# User_LEDs.net
KiCad netlist of a schematic drawn in Altium Designer
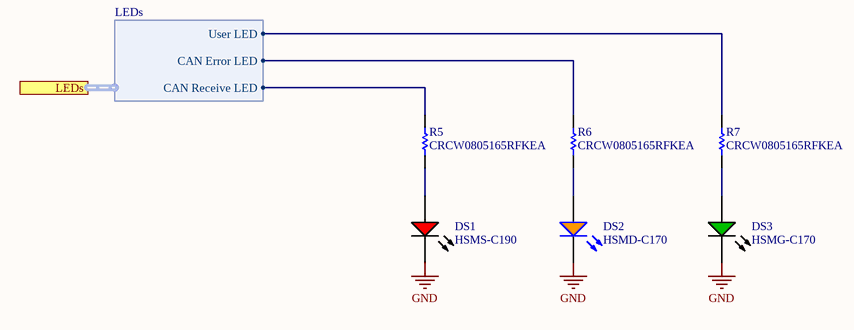
[diagram p0: User_LEDs.SchDoc]

(export (version "E")
  (design (tool "Eeschema 10.0.6"))
  (components
    (comp (ref "DS1")
      (value "HSMS-C190")
      (footprint "AVAG-HSMX-C190_V")
      (description "LED Uni-Color Red, 52 mW, 20 mA, -40 to 85 degC, 2-Pin SMD, RoHS, Tape and Reel")
      (fields (field (name "MANUFACTURER") "Avago"))
      (libsource (lib "Altium Content Vault") (part "LED-RED-AK-2"))
    )
    (comp (ref "DS2")
      (value "HSMD-C170")
      (footprint "AVAG-HSMX-C170_V")
      (description "LED Uni-Color Orange, 52 mW, 20 mA, -40 to 85 degC, 2-Pin SMD, RoHS, Tape and Reel")
      (fields (field (name "MANUFACTURER") "Avago"))
      (libsource (lib "Altium Content Vault") (part "LED-ORANGE-AK-2"))
    )
    (comp (ref "DS3")
      (value "HSMG-C170")
      (footprint "AVAG-HSMX-C170_V")
      (description "Chip LED, Green, 2.2 V, -40 to 85 degC, 2-Pin SMD, Pb-Free, Tape and Reel")
      (fields (field (name "MANUFACTURER") "Avago"))
      (libsource (lib "Altium Content Vault") (part "LED_GREEN_A1K2-2"))
    )
    (comp (ref "R5")
      (value "CRCW0805165RFKEA")
      (footprint "RESC2013X50X30ML20T20")
      (fields (field (name "MANUFACTURER") "Vishay Dale"))
      (libsource (lib "Altium Content Vault") (part "RES"))
    )
    (comp (ref "R6")
      (value "CRCW0805165RFKEA")
      (footprint "RESC2013X50X30ML20T20")
      (fields (field (name "MANUFACTURER") "Vishay Dale"))
      (libsource (lib "Altium Content Vault") (part "RES"))
    )
    (comp (ref "R7")
      (value "CRCW0805165RFKEA")
      (footprint "RESC2013X50X30ML20T20")
      (fields (field (name "MANUFACTURER") "Vishay Dale"))
      (libsource (lib "Altium Content Vault") (part "RES"))
    )
  )
  (nets
    (net (code "2") (name "/CAN Error LED") (class "Default")
      (node (ref "R6") (pin "2") (pinfunction "2_2") (pintype "passive"))
    )
    (net (code "3") (name "/CAN Receive LED") (class "Default")
      (node (ref "R5") (pin "2") (pinfunction "2_2") (pintype "passive"))
    )
    (net (code "4") (name "/User LED") (class "Default")
      (node (ref "R7") (pin "2") (pinfunction "2_2") (pintype "passive"))
    )
    (net (code "6") (name "GND") (class "Default")
      (node (ref "DS1") (pin "2") (pinfunction "K_2") (pintype "passive"))
      (node (ref "DS2") (pin "2") (pinfunction "K_2") (pintype "passive"))
      (node (ref "DS3") (pin "2") (pinfunction "K_2") (pintype "passive"))
    )
    (net (code "7") (name "Net-(DS1-A)") (class "Default")
      (node (ref "DS1") (pin "1") (pinfunction "A_1") (pintype "passive"))
      (node (ref "R5") (pin "1") (pinfunction "1_1") (pintype "passive"))
    )
    (net (code "8") (name "Net-(DS2-A)") (class "Default")
      (node (ref "DS2") (pin "1") (pinfunction "A_1") (pintype "passive"))
      (node (ref "R6") (pin "1") (pinfunction "1_1") (pintype "passive"))
    )
    (net (code "9") (name "Net-(DS3-A)") (class "Default")
      (node (ref "DS3") (pin "1") (pinfunction "A_1") (pintype "passive"))
      (node (ref "R7") (pin "1") (pinfunction "1_1") (pintype "passive"))
    )
  )
)
